# LEAKCAM.net
KiCad netlist of a schematic drawn in Altium Designer
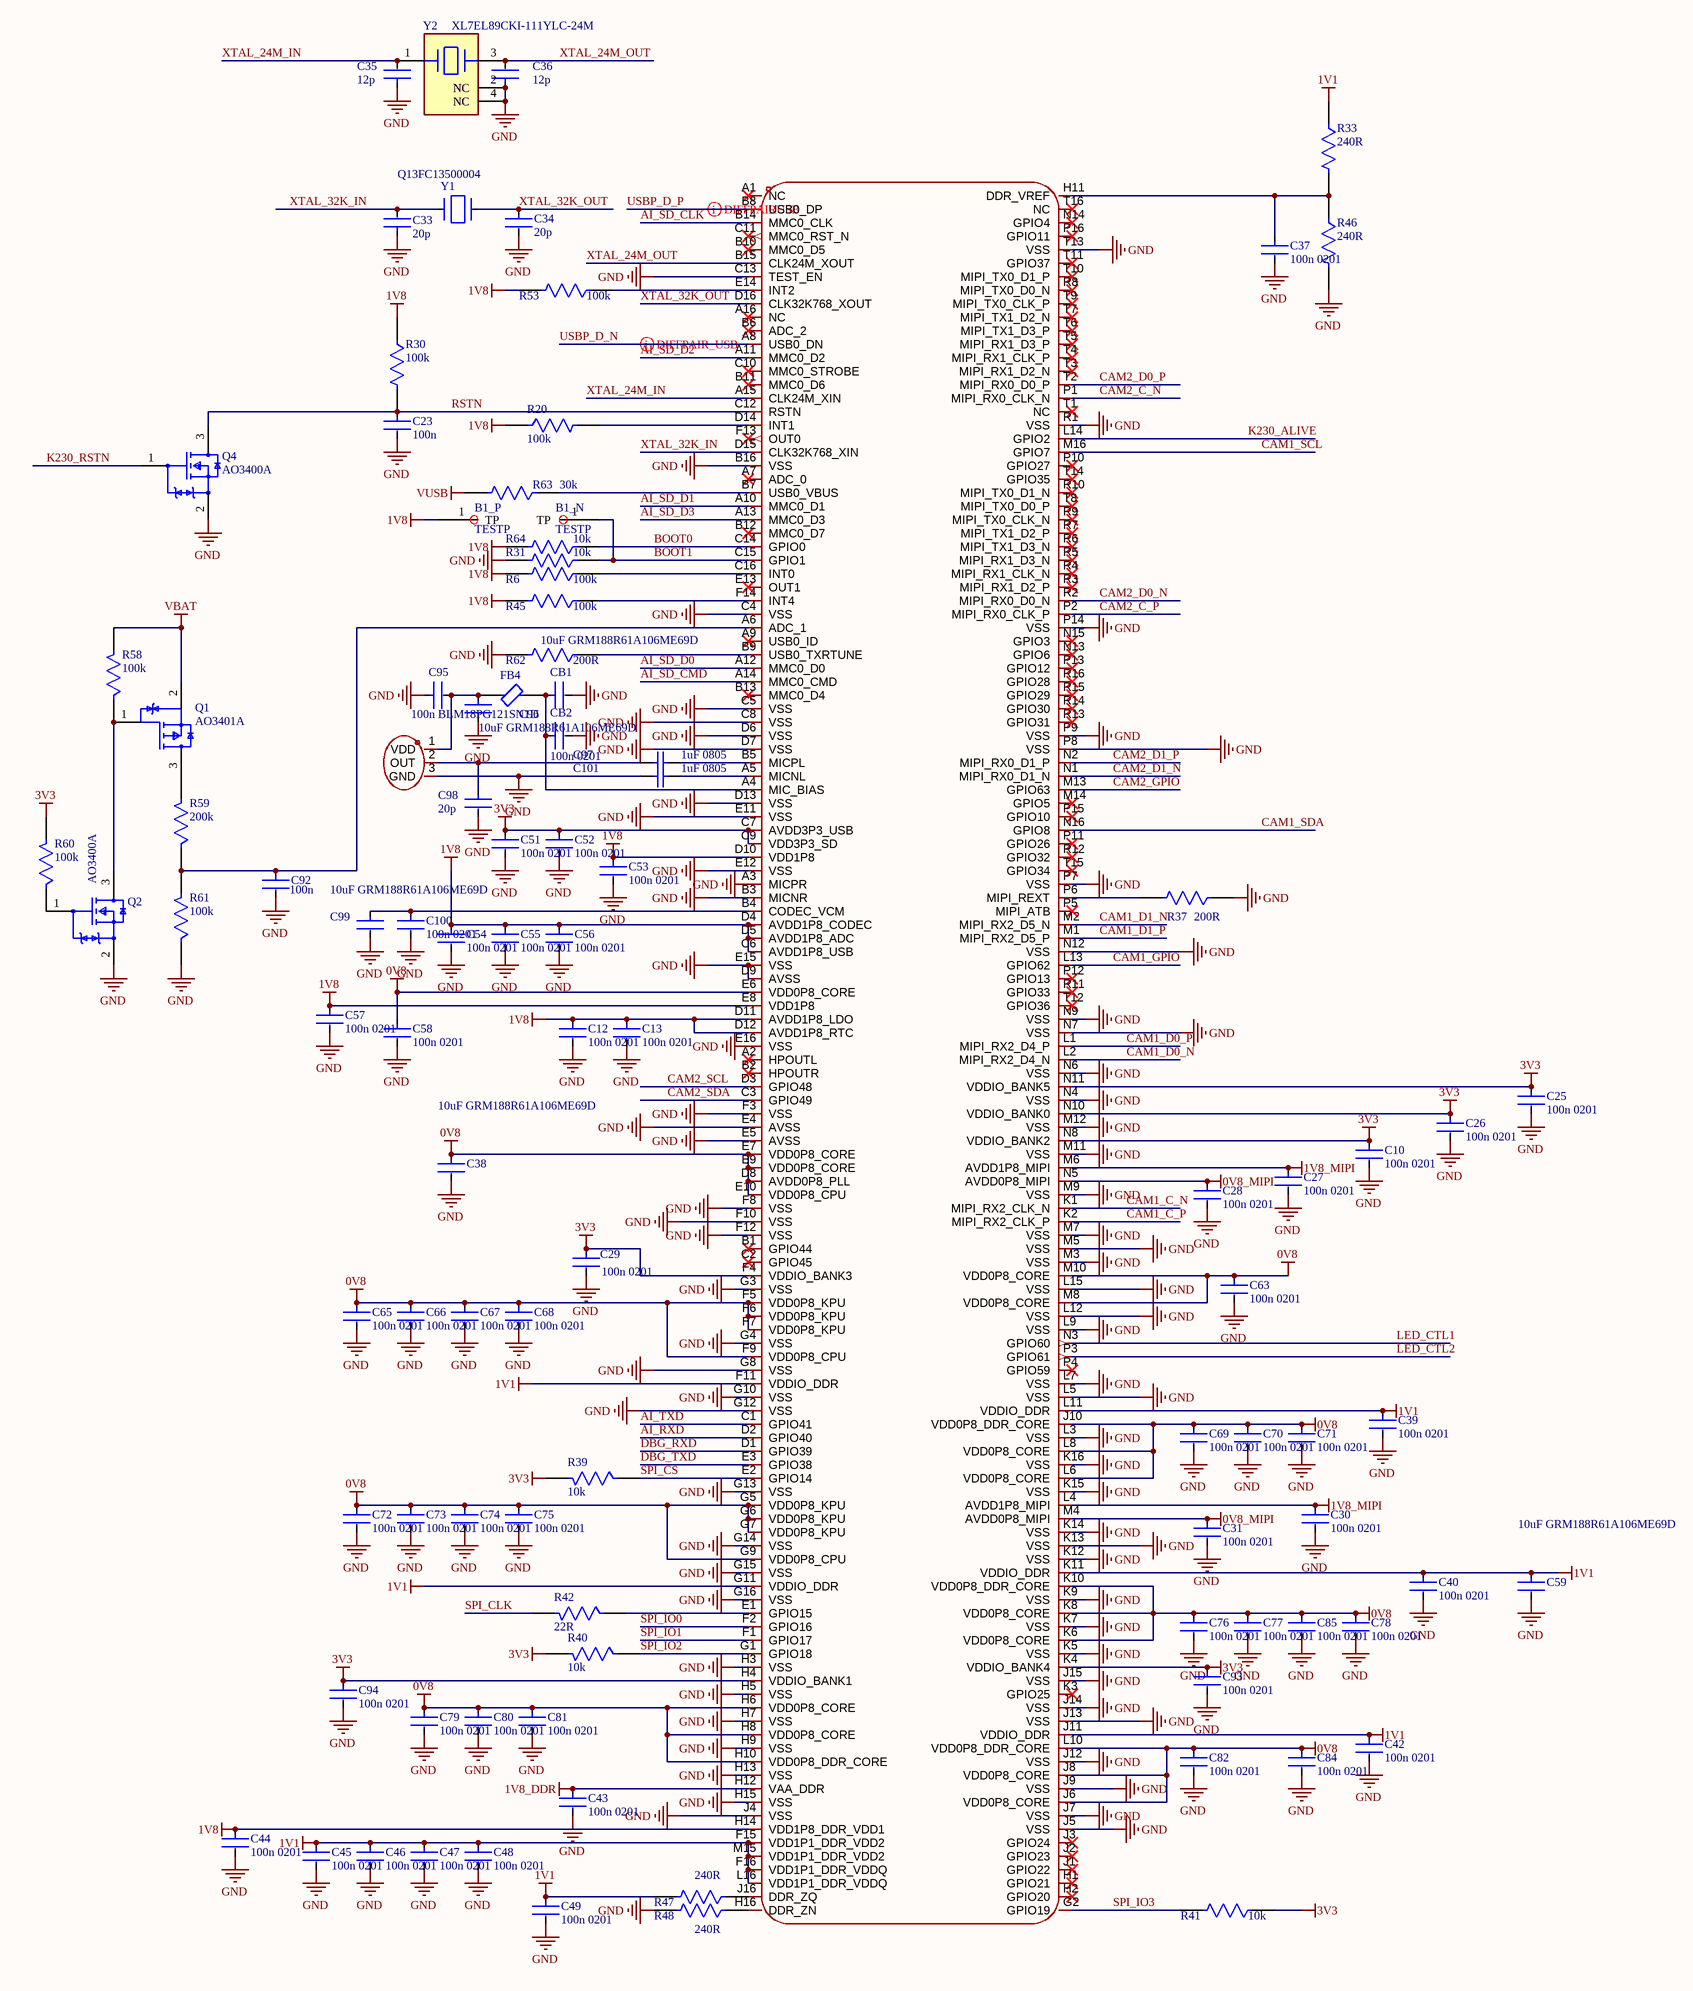
[diagram p0: LEAKCAM.SchDoc]

(export (version "E")
  (design (tool "Eeschema 10.0.6"))
  (components
    (comp (ref "B1_N") (value "TESTP") (footprint "TESTP") (libsource (lib "LEAKCAM") (part "TESTP")))
    (comp (ref "B1_P") (value "TESTP") (footprint "TESTP") (libsource (lib "LEAKCAM") (part "TESTP")))
    (comp (ref "C10")
      (value "100n 0201")
      (footprint "CAP_0201")
      (description "C2903663")
      (fields (field (name "TOLERANCE") "0.1") (field (name "MANUFACTURER") "Yageo"))
      (libsource (lib "LEAKCAM") (part "CMP-03422-001116-1"))
    )
    (comp (ref "C12")
      (value "100n 0201")
      (footprint "CAP_0201")
      (description "C2903663")
      (fields (field (name "TOLERANCE") "0.1") (field (name "MANUFACTURER") "Yageo"))
      (libsource (lib "LEAKCAM") (part "CMP-03422-001116-1"))
    )
    (comp (ref "C13")
      (value "100n 0201")
      (footprint "CAP_0201")
      (description "C2903663")
      (fields (field (name "TOLERANCE") "0.1") (field (name "MANUFACTURER") "Yageo"))
      (libsource (lib "LEAKCAM") (part "CMP-03422-001116-1"))
    )
    (comp (ref "C23")
      (value "100n")
      (footprint "CAP_0402")
      (description "C307331")
      (fields (field (name "TOLERANCE") "10%"))
      (libsource (lib "LEAKCAM") (part "CMP-03422-001116-1"))
    )
    (comp (ref "C25")
      (value "100n 0201")
      (footprint "CAP_0201")
      (description "C2903663")
      (fields (field (name "TOLERANCE") "0.1") (field (name "MANUFACTURER") "Yageo"))
      (libsource (lib "LEAKCAM") (part "CMP-03422-001116-1"))
    )
    (comp (ref "C26")
      (value "100n 0201")
      (footprint "CAP_0201")
      (description "C2903663")
      (fields (field (name "TOLERANCE") "0.1") (field (name "MANUFACTURER") "Yageo"))
      (libsource (lib "LEAKCAM") (part "CMP-03422-001116-1"))
    )
    (comp (ref "C27")
      (value "100n 0201")
      (footprint "CAP_0201")
      (description "C2903663")
      (fields (field (name "TOLERANCE") "0.1") (field (name "MANUFACTURER") "Yageo"))
      (libsource (lib "LEAKCAM") (part "CMP-03422-001116-1"))
    )
    (comp (ref "C28")
      (value "100n 0201")
      (footprint "CAP_0201")
      (description "C2903663")
      (fields (field (name "TOLERANCE") "0.1") (field (name "MANUFACTURER") "Yageo"))
      (libsource (lib "LEAKCAM") (part "CMP-03422-001116-1"))
    )
    (comp (ref "C29")
      (value "100n 0201")
      (footprint "CAP_0201")
      (description "C2903663")
      (fields (field (name "TOLERANCE") "0.1") (field (name "MANUFACTURER") "Yageo"))
      (libsource (lib "LEAKCAM") (part "CMP-03422-001116-1"))
    )
    (comp (ref "C30")
      (value "100n 0201")
      (footprint "CAP_0201")
      (description "C2903663")
      (fields (field (name "TOLERANCE") "0.1") (field (name "MANUFACTURER") "Yageo"))
      (libsource (lib "LEAKCAM") (part "CMP-03422-001116-1"))
    )
    (comp (ref "C31")
      (value "100n 0201")
      (footprint "CAP_0201")
      (description "C2903663")
      (fields (field (name "TOLERANCE") "0.1") (field (name "MANUFACTURER") "Yageo"))
      (libsource (lib "LEAKCAM") (part "CMP-03422-001116-1"))
    )
    (comp (ref "C33")
      (value "20p")
      (footprint "CAP_0402")
      (description "C1554")
      (fields (field (name "TOLERANCE") "10%"))
      (libsource (lib "LEAKCAM") (part "CMP-03422-001116-1"))
    )
    (comp (ref "C34")
      (value "20p")
      (footprint "CAP_0402")
      (description "C1554")
      (fields (field (name "TOLERANCE") "10%"))
      (libsource (lib "LEAKCAM") (part "CMP-03422-001116-1"))
    )
    (comp (ref "C35")
      (value "12p")
      (footprint "CAP_0402")
      (description "C1547")
      (fields (field (name "TOLERANCE") "10%"))
      (libsource (lib "LEAKCAM") (part "CMP-03422-001116-1"))
    )
    (comp (ref "C36")
      (value "12p")
      (footprint "CAP_0402")
      (description "C1547")
      (fields (field (name "TOLERANCE") "10%"))
      (libsource (lib "LEAKCAM") (part "CMP-03422-001116-1"))
    )
    (comp (ref "C37")
      (value "100n 0201")
      (footprint "CAP_0201")
      (description "C2903663")
      (fields (field (name "TOLERANCE") "0.1") (field (name "MANUFACTURER") "Yageo"))
      (libsource (lib "LEAKCAM") (part "CMP-03422-001116-1"))
    )
    (comp (ref "C38")
      (value "10uF GRM188R61A106ME69D")
      (footprint "FP-GRM188-0_15-MFG")
      (description "C19702")
      (fields (field (name "TOLERANCE") "20%"))
      (libsource (lib "LEAKCAM") (part "CMP-06035-003612-1"))
    )
    (comp (ref "C39")
      (value "100n 0201")
      (footprint "CAP_0201")
      (description "C2903663")
      (fields (field (name "TOLERANCE") "0.1") (field (name "MANUFACTURER") "Yageo"))
      (libsource (lib "LEAKCAM") (part "CMP-03422-001116-1"))
    )
    (comp (ref "C40")
      (value "100n 0201")
      (footprint "CAP_0201")
      (description "C2903663")
      (fields (field (name "TOLERANCE") "0.1") (field (name "MANUFACTURER") "Yageo"))
      (libsource (lib "LEAKCAM") (part "CMP-03422-001116-1"))
    )
    (comp (ref "C42")
      (value "100n 0201")
      (footprint "CAP_0201")
      (description "C2903663")
      (fields (field (name "TOLERANCE") "0.1") (field (name "MANUFACTURER") "Yageo"))
      (libsource (lib "LEAKCAM") (part "CMP-03422-001116-1"))
    )
    (comp (ref "C43")
      (value "100n 0201")
      (footprint "CAP_0201")
      (description "C2903663")
      (fields (field (name "TOLERANCE") "0.1") (field (name "MANUFACTURER") "Yageo"))
      (libsource (lib "LEAKCAM") (part "CMP-03422-001116-1"))
    )
    (comp (ref "C44")
      (value "100n 0201")
      (footprint "CAP_0201")
      (description "C2903663")
      (fields (field (name "TOLERANCE") "0.1") (field (name "MANUFACTURER") "Yageo"))
      (libsource (lib "LEAKCAM") (part "CMP-03422-001116-1"))
    )
    (comp (ref "C45")
      (value "100n 0201")
      (footprint "CAP_0201")
      (description "C2903663")
      (fields (field (name "TOLERANCE") "0.1") (field (name "MANUFACTURER") "Yageo"))
      (libsource (lib "LEAKCAM") (part "CMP-03422-001116-1"))
    )
    (comp (ref "C46")
      (value "100n 0201")
      (footprint "CAP_0201")
      (description "C2903663")
      (fields (field (name "TOLERANCE") "0.1") (field (name "MANUFACTURER") "Yageo"))
      (libsource (lib "LEAKCAM") (part "CMP-03422-001116-1"))
    )
    (comp (ref "C47")
      (value "100n 0201")
      (footprint "CAP_0201")
      (description "C2903663")
      (fields (field (name "TOLERANCE") "0.1") (field (name "MANUFACTURER") "Yageo"))
      (libsource (lib "LEAKCAM") (part "CMP-03422-001116-1"))
    )
    (comp (ref "C48")
      (value "100n 0201")
      (footprint "CAP_0201")
      (description "C2903663")
      (fields (field (name "TOLERANCE") "0.1") (field (name "MANUFACTURER") "Yageo"))
      (libsource (lib "LEAKCAM") (part "CMP-03422-001116-1"))
    )
    (comp (ref "C49")
      (value "100n 0201")
      (footprint "CAP_0201")
      (description "C2903663")
      (fields (field (name "TOLERANCE") "0.1") (field (name "MANUFACTURER") "Yageo"))
      (libsource (lib "LEAKCAM") (part "CMP-03422-001116-1"))
    )
    (comp (ref "C51")
      (value "100n 0201")
      (footprint "CAP_0201")
      (description "C2903663")
      (fields (field (name "TOLERANCE") "0.1") (field (name "MANUFACTURER") "Yageo"))
      (libsource (lib "LEAKCAM") (part "CMP-03422-001116-1"))
    )
    (comp (ref "C52")
      (value "100n 0201")
      (footprint "CAP_0201")
      (description "C2903663")
      (fields (field (name "TOLERANCE") "0.1") (field (name "MANUFACTURER") "Yageo"))
      (libsource (lib "LEAKCAM") (part "CMP-03422-001116-1"))
    )
    (comp (ref "C53")
      (value "100n 0201")
      (footprint "CAP_0201")
      (description "C2903663")
      (fields (field (name "TOLERANCE") "0.1") (field (name "MANUFACTURER") "Yageo"))
      (libsource (lib "LEAKCAM") (part "CMP-03422-001116-1"))
    )
    (comp (ref "C54")
      (value "100n 0201")
      (footprint "CAP_0201")
      (description "C2903663")
      (fields (field (name "TOLERANCE") "0.1") (field (name "MANUFACTURER") "Yageo"))
      (libsource (lib "LEAKCAM") (part "CMP-03422-001116-1"))
    )
    (comp (ref "C55")
      (value "100n 0201")
      (footprint "CAP_0201")
      (description "C2903663")
      (fields (field (name "TOLERANCE") "0.1") (field (name "MANUFACTURER") "Yageo"))
      (libsource (lib "LEAKCAM") (part "CMP-03422-001116-1"))
    )
    (comp (ref "C56")
      (value "100n 0201")
      (footprint "CAP_0201")
      (description "C2903663")
      (fields (field (name "TOLERANCE") "0.1") (field (name "MANUFACTURER") "Yageo"))
      (libsource (lib "LEAKCAM") (part "CMP-03422-001116-1"))
    )
    (comp (ref "C57")
      (value "100n 0201")
      (footprint "CAP_0201")
      (description "C2903663")
      (fields (field (name "TOLERANCE") "0.1") (field (name "MANUFACTURER") "Yageo"))
      (libsource (lib "LEAKCAM") (part "CMP-03422-001116-1"))
    )
    (comp (ref "C58")
      (value "100n 0201")
      (footprint "CAP_0201")
      (description "C2903663")
      (fields (field (name "TOLERANCE") "0.1") (field (name "MANUFACTURER") "Yageo"))
      (libsource (lib "LEAKCAM") (part "CMP-03422-001116-1"))
    )
    (comp (ref "C59")
      (value "10uF GRM188R61A106ME69D")
      (footprint "FP-GRM188-0_15-MFG")
      (description "C19702")
      (fields (field (name "TOLERANCE") "20%"))
      (libsource (lib "LEAKCAM") (part "CMP-06035-003612-1"))
    )
    (comp (ref "C63")
      (value "100n 0201")
      (footprint "CAP_0201")
      (description "C2903663")
      (fields (field (name "TOLERANCE") "0.1") (field (name "MANUFACTURER") "Yageo"))
      (libsource (lib "LEAKCAM") (part "CMP-03422-001116-1"))
    )
    (comp (ref "C65")
      (value "100n 0201")
      (footprint "CAP_0201")
      (description "C2903663")
      (fields (field (name "TOLERANCE") "0.1") (field (name "MANUFACTURER") "Yageo"))
      (libsource (lib "LEAKCAM") (part "CMP-03422-001116-1"))
    )
    (comp (ref "C66")
      (value "100n 0201")
      (footprint "CAP_0201")
      (description "C2903663")
      (fields (field (name "TOLERANCE") "0.1") (field (name "MANUFACTURER") "Yageo"))
      (libsource (lib "LEAKCAM") (part "CMP-03422-001116-1"))
    )
    (comp (ref "C67")
      (value "100n 0201")
      (footprint "CAP_0201")
      (description "C2903663")
      (fields (field (name "TOLERANCE") "0.1") (field (name "MANUFACTURER") "Yageo"))
      (libsource (lib "LEAKCAM") (part "CMP-03422-001116-1"))
    )
    (comp (ref "C68")
      (value "100n 0201")
      (footprint "CAP_0201")
      (description "C2903663")
      (fields (field (name "TOLERANCE") "0.1") (field (name "MANUFACTURER") "Yageo"))
      (libsource (lib "LEAKCAM") (part "CMP-03422-001116-1"))
    )
    (comp (ref "C69")
      (value "100n 0201")
      (footprint "CAP_0201")
      (description "C2903663")
      (fields (field (name "TOLERANCE") "0.1") (field (name "MANUFACTURER") "Yageo"))
      (libsource (lib "LEAKCAM") (part "CMP-03422-001116-1"))
    )
    (comp (ref "C70")
      (value "100n 0201")
      (footprint "CAP_0201")
      (description "C2903663")
      (fields (field (name "TOLERANCE") "0.1") (field (name "MANUFACTURER") "Yageo"))
      (libsource (lib "LEAKCAM") (part "CMP-03422-001116-1"))
    )
    (comp (ref "C71")
      (value "100n 0201")
      (footprint "CAP_0201")
      (description "C2903663")
      (fields (field (name "TOLERANCE") "0.1") (field (name "MANUFACTURER") "Yageo"))
      (libsource (lib "LEAKCAM") (part "CMP-03422-001116-1"))
    )
    (comp (ref "C72")
      (value "100n 0201")
      (footprint "CAP_0201")
      (description "C2903663")
      (fields (field (name "TOLERANCE") "0.1") (field (name "MANUFACTURER") "Yageo"))
      (libsource (lib "LEAKCAM") (part "CMP-03422-001116-1"))
    )
    (comp (ref "C73")
      (value "100n 0201")
      (footprint "CAP_0201")
      (description "C2903663")
      (fields (field (name "TOLERANCE") "0.1") (field (name "MANUFACTURER") "Yageo"))
      (libsource (lib "LEAKCAM") (part "CMP-03422-001116-1"))
    )
    (comp (ref "C74")
      (value "100n 0201")
      (footprint "CAP_0201")
      (description "C2903663")
      (fields (field (name "TOLERANCE") "0.1") (field (name "MANUFACTURER") "Yageo"))
      (libsource (lib "LEAKCAM") (part "CMP-03422-001116-1"))
    )
    (comp (ref "C75")
      (value "100n 0201")
      (footprint "CAP_0201")
      (description "C2903663")
      (fields (field (name "TOLERANCE") "0.1") (field (name "MANUFACTURER") "Yageo"))
      (libsource (lib "LEAKCAM") (part "CMP-03422-001116-1"))
    )
    (comp (ref "C76")
      (value "100n 0201")
      (footprint "CAP_0201")
      (description "C2903663")
      (fields (field (name "TOLERANCE") "0.1") (field (name "MANUFACTURER") "Yageo"))
      (libsource (lib "LEAKCAM") (part "CMP-03422-001116-1"))
    )
    (comp (ref "C77")
      (value "100n 0201")
      (footprint "CAP_0201")
      (description "C2903663")
      (fields (field (name "TOLERANCE") "0.1") (field (name "MANUFACTURER") "Yageo"))
      (libsource (lib "LEAKCAM") (part "CMP-03422-001116-1"))
    )
    (comp (ref "C78")
      (value "100n 0201")
      (footprint "CAP_0201")
      (description "C2903663")
      (fields (field (name "TOLERANCE") "0.1") (field (name "MANUFACTURER") "Yageo"))
      (libsource (lib "LEAKCAM") (part "CMP-03422-001116-1"))
    )
    (comp (ref "C79")
      (value "100n 0201")
      (footprint "CAP_0201")
      (description "C2903663")
      (fields (field (name "TOLERANCE") "0.1") (field (name "MANUFACTURER") "Yageo"))
      (libsource (lib "LEAKCAM") (part "CMP-03422-001116-1"))
    )
    (comp (ref "C80")
      (value "100n 0201")
      (footprint "CAP_0201")
      (description "C2903663")
      (fields (field (name "TOLERANCE") "0.1") (field (name "MANUFACTURER") "Yageo"))
      (libsource (lib "LEAKCAM") (part "CMP-03422-001116-1"))
    )
    (comp (ref "C81")
      (value "100n 0201")
      (footprint "CAP_0201")
      (description "C2903663")
      (fields (field (name "TOLERANCE") "0.1") (field (name "MANUFACTURER") "Yageo"))
      (libsource (lib "LEAKCAM") (part "CMP-03422-001116-1"))
    )
    (comp (ref "C82")
      (value "100n 0201")
      (footprint "CAP_0201")
      (description "C2903663")
      (fields (field (name "TOLERANCE") "0.1") (field (name "MANUFACTURER") "Yageo"))
      (libsource (lib "LEAKCAM") (part "CMP-03422-001116-1"))
    )
    (comp (ref "C84")
      (value "100n 0201")
      (footprint "CAP_0201")
      (description "C2903663")
      (fields (field (name "TOLERANCE") "0.1") (field (name "MANUFACTURER") "Yageo"))
      (libsource (lib "LEAKCAM") (part "CMP-03422-001116-1"))
    )
    (comp (ref "C85")
      (value "100n 0201")
      (footprint "CAP_0201")
      (description "C2903663")
      (fields (field (name "TOLERANCE") "0.1") (field (name "MANUFACTURER") "Yageo"))
      (libsource (lib "LEAKCAM") (part "CMP-03422-001116-1"))
    )
    (comp (ref "C92")
      (value "100n")
      (footprint "CAP_0402")
      (description "C307331")
      (fields (field (name "TOLERANCE") "10%"))
      (libsource (lib "LEAKCAM") (part "CMP-03422-001116-1"))
    )
    (comp (ref "C93")
      (value "100n 0201")
      (footprint "CAP_0201")
      (description "C2903663")
      (fields (field (name "TOLERANCE") "0.1") (field (name "MANUFACTURER") "Yageo"))
      (libsource (lib "LEAKCAM") (part "CMP-03422-001116-1"))
    )
    (comp (ref "C94")
      (value "100n 0201")
      (footprint "CAP_0201")
      (description "C2903663")
      (fields (field (name "TOLERANCE") "0.1") (field (name "MANUFACTURER") "Yageo"))
      (libsource (lib "LEAKCAM") (part "CMP-03422-001116-1"))
    )
    (comp (ref "C95")
      (value "100n")
      (footprint "CAP_0402")
      (description "C307331")
      (fields (field (name "TOLERANCE") "10%"))
      (libsource (lib "LEAKCAM") (part "CMP-03422-001116-1"))
    )
    (comp (ref "C96")
      (value "10uF GRM188R61A106ME69D")
      (footprint "FP-GRM188-0_15-MFG")
      (description "C19702")
      (fields (field (name "TOLERANCE") "20%"))
      (libsource (lib "LEAKCAM") (part "CMP-06035-003612-1"))
    )
    (comp (ref "C97")
      (value "1uF 0805")
      (footprint "CAPC2013X145X50NL20T20")
      (description "C28323")
      (fields (field (name "PART NUMBER") "VJ0805Y105KXQRW1BC") (field (name "MANUFACTURER") "Vitramon"))
      (libsource (lib "LEAKCAM") (part "CMP-2007-01676-1"))
    )
    (comp (ref "C98")
      (value "20p")
      (footprint "CAP_0402")
      (description "C1554")
      (fields (field (name "TOLERANCE") "10%"))
      (libsource (lib "LEAKCAM") (part "CMP-03422-001116-1"))
    )
    (comp (ref "C99")
      (value "10uF GRM188R61A106ME69D")
      (footprint "FP-GRM188-0_15-MFG")
      (description "C19702")
      (fields (field (name "TOLERANCE") "20%"))
      (libsource (lib "LEAKCAM") (part "CMP-06035-003612-1"))
    )
    (comp (ref "C100")
      (value "100n 0201")
      (footprint "CAP_0201")
      (description "C2903663")
      (fields (field (name "TOLERANCE") "0.1") (field (name "MANUFACTURER") "Yageo"))
      (libsource (lib "LEAKCAM") (part "CMP-03422-001116-1"))
    )
    (comp (ref "C101")
      (value "1uF 0805")
      (footprint "CAPC2013X145X50NL20T20")
      (description "C28323")
      (fields (field (name "PART NUMBER") "VJ0805Y105KXQRW1BC") (field (name "MANUFACTURER") "Vitramon"))
      (libsource (lib "LEAKCAM") (part "CMP-2007-01676-1"))
    )
    (comp (ref "CB1")
      (value "10uF GRM188R61A106ME69D")
      (footprint "FP-GRM188-0_15-MFG")
      (description "C19702")
      (fields (field (name "TOLERANCE") "20%"))
      (libsource (lib "LEAKCAM") (part "CMP-06035-003612-1"))
    )
    (comp (ref "CB2")
      (value "100n 0201")
      (footprint "CAP_0201")
      (description "C2903663")
      (fields (field (name "TOLERANCE") "0.1") (field (name "MANUFACTURER") "Yageo"))
      (libsource (lib "LEAKCAM") (part "CMP-03422-001116-1"))
    )
    (comp (ref "FB4")
      (value "BLM18PG121SN1D")
      (footprint "FP-BLM18-0_15-t0_8-IPC_B")
      (description "C14709")
      (fields (field (name "TOLERANCE") "25%"))
      (libsource (lib "LEAKCAM") (part "CMP-0686-00439-3"))
    )
    (comp (ref "Q1")
      (value "AO3401A")
      (footprint "FP-SOT23-IPC_B")
      (description "C15127")
      (libsource (lib "LEAKCAM") (part "CMP-12801-000081-1"))
    )
    (comp (ref "Q2")
      (value "AO3400A")
      (footprint "FP-SOT23-MFG")
      (description "C20917")
      (fields
        (field (name "MANUFACTURER PART NUMBER") "DMG2302UK-7")
        (field (name "OCTOPART") "https://octopart.com/dmg2302uk-7-diodes+inc.-73850182")
      )
      (libsource (lib "LEAKCAM") (part "CMP-12801-000001-1"))
    )
    (comp (ref "Q4")
      (value "AO3400A")
      (footprint "FP-SOT23-MFG")
      (description "C20917")
      (fields
        (field (name "MANUFACTURER PART NUMBER") "DMG2302UK-7")
        (field (name "OCTOPART") "https://octopart.com/dmg2302uk-7-diodes+inc.-73850182")
      )
      (libsource (lib "LEAKCAM") (part "CMP-12801-000001-1"))
    )
    (comp (ref "R6")
      (value "100k")
      (footprint "RES_0402")
      (description "C25741")
      (fields (field (name "TOLERANCE") "1%"))
      (libsource (lib "LEAKCAM") (part "CMP-03412-016018-1"))
    )
    (comp (ref "R20")
      (value "100k")
      (footprint "RES_0402")
      (description "C25741")
      (fields (field (name "TOLERANCE") "1%"))
      (libsource (lib "LEAKCAM") (part "CMP-03412-016018-1"))
    )
    (comp (ref "R30")
      (value "100k")
      (footprint "RES_0402")
      (description "C25741")
      (fields (field (name "TOLERANCE") "1%"))
      (libsource (lib "LEAKCAM") (part "CMP-03412-016018-1"))
    )
    (comp (ref "R31")
      (value "10k")
      (footprint "RES_0402")
      (description "C25744")
      (fields (field (name "TOLERANCE") "1%"))
      (libsource (lib "LEAKCAM") (part "CMP-03412-016018-1"))
    )
    (comp (ref "R33")
      (value "240R")
      (footprint "RES_0402")
      (description "C324768")
      (fields (field (name "TOLERANCE") "1%"))
      (libsource (lib "LEAKCAM") (part "CMP-03412-016018-1"))
    )
    (comp (ref "R37")
      (value "200R")
      (footprint "RES_0402")
      (description "C25087")
      (fields (field (name "TOLERANCE") "1%"))
      (libsource (lib "LEAKCAM") (part "CMP-03412-016018-1"))
    )
    (comp (ref "R39")
      (value "10k")
      (footprint "RES_0402")
      (description "C25744")
      (fields (field (name "TOLERANCE") "1%"))
      (libsource (lib "LEAKCAM") (part "CMP-03412-016018-1"))
    )
    (comp (ref "R40")
      (value "10k")
      (footprint "RES_0402")
      (description "C25744")
      (fields (field (name "TOLERANCE") "1%"))
      (libsource (lib "LEAKCAM") (part "CMP-03412-016018-1"))
    )
    (comp (ref "R41")
      (value "10k")
      (footprint "RES_0402")
      (description "C25744")
      (fields (field (name "TOLERANCE") "1%"))
      (libsource (lib "LEAKCAM") (part "CMP-03412-016018-1"))
    )
    (comp (ref "R42")
      (value "22R")
      (footprint "RES_0402")
      (description "C25092")
      (fields (field (name "TOLERANCE") "1%"))
      (libsource (lib "LEAKCAM") (part "CMP-03412-016018-1"))
    )
    (comp (ref "R45")
      (value "100k")
      (footprint "RES_0402")
      (description "C25741")
      (fields (field (name "TOLERANCE") "1%"))
      (libsource (lib "LEAKCAM") (part "CMP-03412-016018-1"))
    )
    (comp (ref "R46")
      (value "240R")
      (footprint "RES_0402")
      (description "C324768")
      (fields (field (name "TOLERANCE") "1%"))
      (libsource (lib "LEAKCAM") (part "CMP-03412-016018-1"))
    )
    (comp (ref "R47")
      (value "240R")
      (footprint "RES_0402")
      (description "C324768")
      (fields (field (name "TOLERANCE") "1%"))
      (libsource (lib "LEAKCAM") (part "CMP-03412-016018-1"))
    )
    (comp (ref "R48")
      (value "240R")
      (footprint "RES_0402")
      (description "C324768")
      (fields (field (name "TOLERANCE") "1%"))
      (libsource (lib "LEAKCAM") (part "CMP-03412-016018-1"))
    )
    (comp (ref "R53")
      (value "100k")
      (footprint "RES_0402")
      (description "C25741")
      (fields (field (name "TOLERANCE") "1%"))
      (libsource (lib "LEAKCAM") (part "CMP-03412-016018-1"))
    )
    (comp (ref "R58")
      (value "100k")
      (footprint "RES_0402")
      (description "C25741")
      (fields (field (name "TOLERANCE") "1%"))
      (libsource (lib "LEAKCAM") (part "CMP-03412-016018-1"))
    )
    (comp (ref "R59")
      (value "200k")
      (footprint "RES_0402")
      (description "C25764")
      (fields (field (name "TOLERANCE") "1%"))
      (libsource (lib "LEAKCAM") (part "CMP-03412-016018-1"))
    )
    (comp (ref "R60")
      (value "100k")
      (footprint "RES_0402")
      (description "C25741")
      (fields (field (name "TOLERANCE") "1%"))
      (libsource (lib "LEAKCAM") (part "CMP-03412-016018-1"))
    )
    (comp (ref "R61")
      (value "100k")
      (footprint "RES_0402")
      (description "C25741")
      (fields (field (name "TOLERANCE") "1%"))
      (libsource (lib "LEAKCAM") (part "CMP-03412-016018-1"))
    )
    (comp (ref "R62")
      (value "200R")
      (footprint "RES_0402")
      (description "C25087")
      (fields (field (name "TOLERANCE") "1%"))
      (libsource (lib "LEAKCAM") (part "CMP-03412-016018-1"))
    )
    (comp (ref "R63")
      (value "30k")
      (footprint "RES_0402")
      (description "C49653548")
      (fields (field (name "TOLERANCE") "1%"))
      (libsource (lib "LEAKCAM") (part "CMP-03412-016018-1"))
    )
    (comp (ref "R64")
      (value "10k")
      (footprint "RES_0402")
      (description "C25744")
      (fields (field (name "TOLERANCE") "1%"))
      (libsource (lib "LEAKCAM") (part "CMP-03412-016018-1"))
    )
    (comp (ref "U3")
      (value "k230d")
      (footprint "K230D")
      (description "C42414902")
      (fields (field (name "MANUFACTURER") "Canaan(嘉楠)") (field (name "MANUFACTURERPART") "K230D"))
      (libsource (lib "LEAKCAM") (part "k230d"))
    )
    (comp (ref "U13")
      (value "msm381acb026")
      (footprint "mems")
      (description "C51928208")
      (fields (field (name "MANUFACTURER") "MEMS(敏芯微)") (field (name "MANUFACTURERPART") "MSM381ACB026"))
      (libsource (lib "LEAKCAM") (part "msm381acb026"))
    )
    (comp (ref "Y1")
      (value "Q13FC13500004")
      (footprint "FP-ABS07-MFG")
      (description "C32346")
      (fields (field (name "TOLERANCE") "20ppm"))
      (libsource (lib "LEAKCAM") (part "CMP-0447-00001-4"))
    )
    (comp (ref "Y2")
      (value "XL7EL89CKI-111YLC-24M")
      (footprint "FP-XRCGB_F_N-MFG")
      (description "C2965580")
      (fields (field (name "TOLERANCE") "30ppm"))
      (libsource (lib "LEAKCAM") (part "CMP-06054-000017-1"))
    )
  )
  (nets
    (net (code "1") (name "/AI_RXD") (class "Default")
      (node (ref "U3") (pin "D2") (pinfunction "GPIO40_D2") (pintype "passive"))
    )
    (net (code "2") (name "/AI_SD_CLK") (class "Default")
      (node (ref "U3") (pin "B14") (pinfunction "MMC0_CLK_B14") (pintype "passive"))
    )
    (net (code "3") (name "/AI_SD_CMD") (class "Default")
      (node (ref "U3") (pin "A14") (pinfunction "MMC0_CMD_A14") (pintype "passive"))
    )
    (net (code "4") (name "/AI_SD_D0") (class "Default")
      (node (ref "U3") (pin "A12") (pinfunction "MMC0_D0_A12") (pintype "passive"))
    )
    (net (code "5") (name "/AI_SD_D1") (class "Default")
      (node (ref "U3") (pin "A10") (pinfunction "MMC0_D1_A10") (pintype "passive"))
    )
    (net (code "6") (name "/AI_SD_D2") (class "Default")
      (node (ref "U3") (pin "A11") (pinfunction "MMC0_D2_A11") (pintype "passive"))
    )
    (net (code "7") (name "/AI_SD_D3") (class "Default")
      (node (ref "U3") (pin "A13") (pinfunction "MMC0_D3_A13") (pintype "passive"))
    )
    (net (code "8") (name "/AI_TXD") (class "Default")
      (node (ref "U3") (pin "C1") (pinfunction "GPIO41_C1") (pintype "passive"))
    )
    (net (code "9") (name "/BOOT0") (class "Default")
      (node (ref "R64") (pin "1") (pinfunction "1_1") (pintype "passive"))
      (node (ref "U3") (pin "C14") (pinfunction "GPIO0_C14") (pintype "passive"))
    )
    (net (code "10") (name "/BOOT1") (class "Default")
      (node (ref "B1_N") (pin "1") (pinfunction "TP_1") (pintype "passive"))
      (node (ref "R31") (pin "1") (pinfunction "1_1") (pintype "passive"))
      (node (ref "U3") (pin "C15") (pinfunction "GPIO1_C15") (pintype "passive"))
    )
    (net (code "11") (name "/CAM1_C_N") (class "Default")
      (node (ref "U3") (pin "K1") (pinfunction "MIPI_RX2_CLK_N_K1") (pintype "passive"))
    )
    (net (code "12") (name "/CAM1_C_P") (class "Default")
      (node (ref "U3") (pin "K2") (pinfunction "MIPI_RX2_CLK_P_K2") (pintype "passive"))
    )
    (net (code "13") (name "/CAM1_D0_N") (class "Default")
      (node (ref "U3") (pin "L2") (pinfunction "MIPI_RX2_D4_N_L2") (pintype "passive"))
    )
    (net (code "14") (name "/CAM1_D0_P") (class "Default")
      (node (ref "U3") (pin "L1") (pinfunction "MIPI_RX2_D4_P_L1") (pintype "passive"))
    )
    (net (code "15") (name "/CAM1_D1_N") (class "Default")
      (node (ref "U3") (pin "M2") (pinfunction "MIPI_RX2_D5_N_M2") (pintype "passive"))
    )
    (net (code "16") (name "/CAM1_D1_P") (class "Default")
      (node (ref "U3") (pin "M1") (pinfunction "MIPI_RX2_D5_P_M1") (pintype "passive"))
    )
    (net (code "17") (name "/CAM1_GPIO") (class "Default")
      (node (ref "U3") (pin "L13") (pinfunction "GPIO62_L13") (pintype "passive"))
    )
    (net (code "18") (name "/CAM1_SCL") (class "Default")
      (node (ref "U3") (pin "M16") (pinfunction "GPIO7_M16") (pintype "passive"))
    )
    (net (code "19") (name "/CAM1_SDA") (class "Default")
      (node (ref "U3") (pin "N16") (pinfunction "GPIO8_N16") (pintype "passive"))
    )
    (net (code "20") (name "/CAM2_C_N") (class "Default")
      (node (ref "U3") (pin "P1") (pinfunction "MIPI_RX0_CLK_N_P1") (pintype "passive"))
    )
    (net (code "21") (name "/CAM2_C_P") (class "Default")
      (node (ref "U3") (pin "P2") (pinfunction "MIPI_RX0_CLK_P_P2") (pintype "passive"))
    )
    (net (code "22") (name "/CAM2_D0_N") (class "Default")
      (node (ref "U3") (pin "R2") (pinfunction "MIPI_RX0_D0_N_R2") (pintype "passive"))
    )
    (net (code "23") (name "/CAM2_D0_P") (class "Default")
      (node (ref "U3") (pin "T2") (pinfunction "MIPI_RX0_D0_P_T2") (pintype "passive"))
    )
    (net (code "24") (name "/CAM2_D1_N") (class "Default")
      (node (ref "U3") (pin "N1") (pinfunction "MIPI_RX0_D1_N_N1") (pintype "passive"))
    )
    (net (code "25") (name "/CAM2_D1_P") (class "Default")
      (node (ref "U3") (pin "N2") (pinfunction "MIPI_RX0_D1_P_N2") (pintype "passive"))
    )
    (net (code "26") (name "/CAM2_GPIO") (class "Default")
      (node (ref "U3") (pin "M13") (pinfunction "GPIO63_M13") (pintype "passive"))
    )
    (net (code "27") (name "/CAM2_SCL") (class "Default")
      (node (ref "U3") (pin "D3") (pinfunction "GPIO48_D3") (pintype "passive"))
    )
    (net (code "28") (name "/CAM2_SDA") (class "Default")
      (node (ref "U3") (pin "C3") (pinfunction "GPIO49_C3") (pintype "passive"))
    )
    (net (code "29") (name "/DBG_RXD") (class "Default")
      (node (ref "U3") (pin "D1") (pinfunction "GPIO39_D1") (pintype "passive"))
    )
    (net (code "30") (name "/DBG_TXD") (class "Default")
      (node (ref "U3") (pin "E3") (pinfunction "GPIO38_E3") (pintype "passive"))
    )
    (net (code "31") (name "/K230_ALIVE") (class "Default")
      (node (ref "U3") (pin "L14") (pinfunction "GPIO2_L14") (pintype "passive"))
    )
    (net (code "32") (name "/K230_RSTN") (class "Default")
      (node (ref "Q4") (pin "1") (pinfunction "G_1") (pintype "passive"))
    )
    (net (code "33") (name "/LED_CTL1") (class "Default")
      (node (ref "U3") (pin "N3") (pinfunction "GPIO60_N3") (pintype "output"))
    )
    (net (code "34") (name "/LED_CTL2") (class "Default")
      (node (ref "U3") (pin "P3") (pinfunction "GPIO61_P3") (pintype "output"))
    )
    (net (code "35") (name "/RSTN") (class "Default")
      (node (ref "C23") (pin "1") (pinfunction "1_1") (pintype "passive"))
      (node (ref "Q4") (pin "3") (pinfunction "D_3") (pintype "passive"))
      (node (ref "R30") (pin "2") (pinfunction "2_2") (pintype "passive"))
      (node (ref "U3") (pin "C12") (pinfunction "RSTN_C12") (pintype "passive"))
    )
    (net (code "36") (name "/SPI_CLK") (class "Default")
      (node (ref "R42") (pin "2") (pinfunction "2_2") (pintype "passive"))
    )
    (net (code "37") (name "/SPI_CS") (class "Default")
      (node (ref "R39") (pin "1") (pinfunction "1_1") (pintype "passive"))
      (node (ref "U3") (pin "E2") (pinfunction "GPIO14_E2") (pintype "passive"))
    )
    (net (code "38") (name "/SPI_IO0") (class "Default")
      (node (ref "U3") (pin "F2") (pinfunction "GPIO16_F2") (pintype "passive"))
    )
    (net (code "39") (name "/SPI_IO1") (class "Default")
      (node (ref "U3") (pin "F1") (pinfunction "GPIO17_F1") (pintype "passive"))
    )
    (net (code "40") (name "/SPI_IO2") (class "Default")
      (node (ref "R40") (pin "1") (pinfunction "1_1") (pintype "passive"))
      (node (ref "U3") (pin "G1") (pinfunction "GPIO18_G1") (pintype "passive"))
    )
    (net (code "41") (name "/SPI_IO3") (class "Default")
      (node (ref "R41") (pin "2") (pinfunction "2_2") (pintype "passive"))
      (node (ref "U3") (pin "G2") (pinfunction "GPIO19_G2") (pintype "passive"))
    )
    (net (code "42") (name "/USBP_D_N") (class "Default")
      (node (ref "U3") (pin "A8") (pinfunction "USB0_DN_A8") (pintype "passive"))
    )
    (net (code "43") (name "/USBP_D_P") (class "Default")
      (node (ref "U3") (pin "B8") (pinfunction "USB0_DP_B8") (pintype "passive"))
    )
    (net (code "44") (name "/XTAL_24M_IN") (class "Default")
      (node (ref "C35") (pin "2") (pinfunction "2_2") (pintype "passive"))
      (node (ref "U3") (pin "A15") (pinfunction "CLK24M_XIN_A15") (pintype "passive"))
      (node (ref "Y2") (pin "1") (pinfunction "1_Input/Output_1") (pintype "passive"))
    )
    (net (code "45") (name "/XTAL_24M_OUT") (class "Default")
      (node (ref "C36") (pin "2") (pinfunction "2_2") (pintype "passive"))
      (node (ref "U3") (pin "B15") (pinfunction "CLK24M_XOUT_B15") (pintype "passive"))
      (node (ref "Y2") (pin "3") (pinfunction "2_Input/Output_3") (pintype "passive"))
    )
    (net (code "46") (name "/XTAL_32K_IN") (class "Default")
      (node (ref "C33") (pin "2") (pinfunction "2_2") (pintype "passive"))
      (node (ref "U3") (pin "D15") (pinfunction "CLK32K768_XIN_D15") (pintype "passive"))
      (node (ref "Y1") (pin "1") (pinfunction "1_1") (pintype "passive"))
    )
    (net (code "47") (name "/XTAL_32K_OUT") (class "Default")
      (node (ref "C34") (pin "1") (pinfunction "1_1") (pintype "passive"))
      (node (ref "U3") (pin "D16") (pinfunction "CLK32K768_XOUT_D16") (pintype "passive"))
      (node (ref "Y1") (pin "2") (pinfunction "2_2") (pintype "passive"))
    )
    (net (code "48") (name "0V8") (class "Default")
      (node (ref "C38") (pin "1") (pinfunction "1_1") (pintype "passive"))
      (node (ref "C58") (pin "1") (pinfunction "1_1") (pintype "passive"))
      (node (ref "C63") (pin "1") (pinfunction "1_1") (pintype "passive"))
      (node (ref "C65") (pin "1") (pinfunction "1_1") (pintype "passive"))
      (node (ref "C66") (pin "1") (pinfunction "1_1") (pintype "passive"))
      (node (ref "C67") (pin "1") (pinfunction "1_1") (pintype "passive"))
      (node (ref "C68") (pin "1") (pinfunction "1_1") (pintype "passive"))
      (node (ref "C69") (pin "1") (pinfunction "1_1") (pintype "passive"))
      (node (ref "C70") (pin "1") (pinfunction "1_1") (pintype "passive"))
      (node (ref "C71") (pin "1") (pinfunction "1_1") (pintype "passive"))
      (node (ref "C72") (pin "1") (pinfunction "1_1") (pintype "passive"))
      (node (ref "C73") (pin "1") (pinfunction "1_1") (pintype "passive"))
      (node (ref "C74") (pin "1") (pinfunction "1_1") (pintype "passive"))
      (node (ref "C75") (pin "1") (pinfunction "1_1") (pintype "passive"))
      (node (ref "C76") (pin "1") (pinfunction "1_1") (pintype "passive"))
      (node (ref "C77") (pin "1") (pinfunction "1_1") (pintype "passive"))
      (node (ref "C78") (pin "1") (pinfunction "1_1") (pintype "passive"))
      (node (ref "C79") (pin "1") (pinfunction "1_1") (pintype "passive"))
      (node (ref "C80") (pin "1") (pinfunction "1_1") (pintype "passive"))
      (node (ref "C81") (pin "1") (pinfunction "1_1") (pintype "passive"))
      (node (ref "C82") (pin "1") (pinfunction "1_1") (pintype "passive"))
      (node (ref "C84") (pin "1") (pinfunction "1_1") (pintype "passive"))
      (node (ref "C85") (pin "1") (pinfunction "1_1") (pintype "passive"))
      (node (ref "U3") (pin "D8") (pinfunction "AVDD0P8_PLL_D8") (pintype "passive"))
      (node (ref "U3") (pin "E10") (pinfunction "VDD0P8_CPU_E10") (pintype "passive"))
      (node (ref "U3") (pin "E6") (pinfunction "VDD0P8_CORE_E6") (pintype "passive"))
      (node (ref "U3") (pin "E7") (pinfunction "VDD0P8_CORE_E7") (pintype "passive"))
      (node (ref "U3") (pin "E9") (pinfunction "VDD0P8_CORE_E9") (pintype "passive"))
      (node (ref "U3") (pin "F5") (pinfunction "VDD0P8_KPU_F5") (pintype "passive"))
      (node (ref "U3") (pin "F6") (pinfunction "VDD0P8_KPU_F6") (pintype "passive"))
      (node (ref "U3") (pin "F7") (pinfunction "VDD0P8_KPU_F7") (pintype "passive"))
      (node (ref "U3") (pin "F9") (pinfunction "VDD0P8_CPU_F9") (pintype "passive"))
      (node (ref "U3") (pin "G5") (pinfunction "VDD0P8_KPU_G5") (pintype "passive"))
      (node (ref "U3") (pin "G6") (pinfunction "VDD0P8_KPU_G6") (pintype "passive"))
      (node (ref "U3") (pin "G7") (pinfunction "VDD0P8_KPU_G7") (pintype "passive"))
      (node (ref "U3") (pin "G9") (pinfunction "VDD0P8_CPU_G9") (pintype "passive"))
      (node (ref "U3") (pin "H10") (pinfunction "VDD0P8_DDR_CORE_H10") (pintype "passive"))
      (node (ref "U3") (pin "H6") (pinfunction "VDD0P8_CORE_H6") (pintype "passive"))
      (node (ref "U3") (pin "H8") (pinfunction "VDD0P8_CORE_H8") (pintype "passive"))
      (node (ref "U3") (pin "J10") (pinfunction "VDD0P8_DDR_CORE_J10") (pintype "passive"))
      (node (ref "U3") (pin "J6") (pinfunction "VDD0P8_CORE_J6") (pintype "passive"))
      (node (ref "U3") (pin "J8") (pinfunction "VDD0P8_CORE_J8") (pintype "passive"))
      (node (ref "U3") (pin "K10") (pinfunction "VDD0P8_DDR_CORE_K10") (pintype "passive"))
      (node (ref "U3") (pin "K6") (pinfunction "VDD0P8_CORE_K6") (pintype "passive"))
      (node (ref "U3") (pin "K8") (pinfunction "VDD0P8_CORE_K8") (pintype "passive"))
      (node (ref "U3") (pin "L10") (pinfunction "VDD0P8_DDR_CORE_L10") (pintype "passive"))
      (node (ref "U3") (pin "L6") (pinfunction "VDD0P8_CORE_L6") (pintype "passive"))
      (node (ref "U3") (pin "L8") (pinfunction "VDD0P8_CORE_L8") (pintype "passive"))
      (node (ref "U3") (pin "M10") (pinfunction "VDD0P8_CORE_M10") (pintype "passive"))
      (node (ref "U3") (pin "M8") (pinfunction "VDD0P8_CORE_M8") (pintype "passive"))
    )
    (net (code "49") (name "0V8_MIPI") (class "Default")
      (node (ref "C28") (pin "1") (pinfunction "1_1") (pintype "passive"))
      (node (ref "C31") (pin "1") (pinfunction "1_1") (pintype "passive"))
      (node (ref "U3") (pin "M4") (pinfunction "AVDD0P8_MIPI_M4") (pintype "passive"))
      (node (ref "U3") (pin "N5") (pinfunction "AVDD0P8_MIPI_N5") (pintype "passive"))
    )
    (net (code "50") (name "1V1") (class "Default")
      (node (ref "C39") (pin "1") (pinfunction "1_1") (pintype "passive"))
      (node (ref "C40") (pin "1") (pinfunction "1_1") (pintype "passive"))
      (node (ref "C42") (pin "1") (pinfunction "1_1") (pintype "passive"))
      (node (ref "C45") (pin "1") (pinfunction "1_1") (pintype "passive"))
      (node (ref "C46") (pin "1") (pinfunction "1_1") (pintype "passive"))
      (node (ref "C47") (pin "1") (pinfunction "1_1") (pintype "passive"))
      (node (ref "C48") (pin "1") (pinfunction "1_1") (pintype "passive"))
      (node (ref "C49") (pin "1") (pinfunction "1_1") (pintype "passive"))
      (node (ref "C59") (pin "1") (pinfunction "1_1") (pintype "passive"))
      (node (ref "R33") (pin "1") (pinfunction "1_1") (pintype "passive"))
      (node (ref "R47") (pin "2") (pinfunction "2_2") (pintype "passive"))
      (node (ref "U3") (pin "F11") (pinfunction "VDDIO_DDR_F11") (pintype "passive"))
      (node (ref "U3") (pin "F15") (pinfunction "VDD1P1_DDR_VDD2_F15") (pintype "passive"))
      (node (ref "U3") (pin "F16") (pinfunction "VDD1P1_DDR_VDDQ_F16") (pintype "passive"))
      (node (ref "U3") (pin "G11") (pinfunction "VDDIO_DDR_G11") (pintype "passive"))
      (node (ref "U3") (pin "J11") (pinfunction "VDDIO_DDR_J11") (pintype "passive"))
      (node (ref "U3") (pin "K11") (pinfunction "VDDIO_DDR_K11") (pintype "passive"))
      (node (ref "U3") (pin "L11") (pinfunction "VDDIO_DDR_L11") (pintype "passive"))
      (node (ref "U3") (pin "L16") (pinfunction "VDD1P1_DDR_VDDQ_L16") (pintype "passive"))
      (node (ref "U3") (pin "M15") (pinfunction "VDD1P1_DDR_VDD2_M15") (pintype "passive"))
    )
    (net (code "51") (name "1V8") (class "Default")
      (node (ref "B1_P") (pin "1") (pinfunction "TP_1") (pintype "passive"))
      (node (ref "C12") (pin "1") (pinfunction "1_1") (pintype "passive"))
      (node (ref "C13") (pin "1") (pinfunction "1_1") (pintype "passive"))
      (node (ref "C44") (pin "1") (pinfunction "1_1") (pintype "passive"))
      (node (ref "C53") (pin "1") (pinfunction "1_1") (pintype "passive"))
      (node (ref "C54") (pin "1") (pinfunction "1_1") (pintype "passive"))
      (node (ref "C55") (pin "1") (pinfunction "1_1") (pintype "passive"))
      (node (ref "C56") (pin "1") (pinfunction "1_1") (pintype "passive"))
      (node (ref "C57") (pin "1") (pinfunction "1_1") (pintype "passive"))
      (node (ref "R20") (pin "1") (pinfunction "1_1") (pintype "passive"))
      (node (ref "R30") (pin "1") (pinfunction "1_1") (pintype "passive"))
      (node (ref "R45") (pin "2") (pinfunction "2_2") (pintype "passive"))
      (node (ref "R53") (pin "2") (pinfunction "2_2") (pintype "passive"))
      (node (ref "R6") (pin "2") (pinfunction "2_2") (pintype "passive"))
      (node (ref "R64") (pin "2") (pinfunction "2_2") (pintype "passive"))
      (node (ref "U3") (pin "C6") (pinfunction "AVDD1P8_USB_C6") (pintype "passive"))
      (node (ref "U3") (pin "D10") (pinfunction "VDD1P8_D10") (pintype "passive"))
      (node (ref "U3") (pin "D11") (pinfunction "AVDD1P8_LDO_D11") (pintype "passive"))
      (node (ref "U3") (pin "D12") (pinfunction "AVDD1P8_RTC_D12") (pintype "passive"))
      (node (ref "U3") (pin "D4") (pinfunction "AVDD1P8_CODEC_D4") (pintype "passive"))
      (node (ref "U3") (pin "D5") (pinfunction "AVDD1P8_ADC_D5") (pintype "passive"))
      (node (ref "U3") (pin "E8") (pinfunction "VDD1P8_E8") (pintype "passive"))
      (node (ref "U3") (pin "H14") (pinfunction "VDD1P8_DDR_VDD1_H14") (pintype "passive"))
    )
    (net (code "52") (name "1V8_DDR") (class "Default")
      (node (ref "C43") (pin "1") (pinfunction "1_1") (pintype "passive"))
      (node (ref "U3") (pin "H12") (pinfunction "VAA_DDR_H12") (pintype "passive"))
    )
    (net (code "53") (name "1V8_MIPI") (class "Default")
      (node (ref "C27") (pin "1") (pinfunction "1_1") (pintype "passive"))
      (node (ref "C30") (pin "1") (pinfunction "1_1") (pintype "passive"))
      (node (ref "U3") (pin "L4") (pinfunction "AVDD1P8_MIPI_L4") (pintype "passive"))
      (node (ref "U3") (pin "M6") (pinfunction "AVDD1P8_MIPI_M6") (pintype "passive"))
    )
    (net (code "54") (name "3V3") (class "Default")
      (node (ref "C10") (pin "1") (pinfunction "1_1") (pintype "passive"))
      (node (ref "C25") (pin "1") (pinfunction "1_1") (pintype "passive"))
      (node (ref "C26") (pin "1") (pinfunction "1_1") (pintype "passive"))
      (node (ref "C29") (pin "1") (pinfunction "1_1") (pintype "passive"))
      (node (ref "C51") (pin "1") (pinfunction "1_1") (pintype "passive"))
      (node (ref "C52") (pin "1") (pinfunction "1_1") (pintype "passive"))
      (node (ref "C93") (pin "1") (pinfunction "1_1") (pintype "passive"))
      (node (ref "C94") (pin "1") (pinfunction "1_1") (pintype "passive"))
      (node (ref "R39") (pin "2") (pinfunction "2_2") (pintype "passive"))
      (node (ref "R40") (pin "2") (pinfunction "2_2") (pintype "passive"))
      (node (ref "R41") (pin "1") (pinfunction "1_1") (pintype "passive"))
      (node (ref "R60") (pin "2") (pinfunction "2_2") (pintype "passive"))
      (node (ref "U3") (pin "C7") (pinfunction "AVDD3P3_USB_C7") (pintype "passive"))
      (node (ref "U3") (pin "C9") (pinfunction "VDD3P3_SD_C9") (pintype "passive"))
      (node (ref "U3") (pin "F4") (pinfunction "VDDIO_BANK3_F4") (pintype "passive"))
      (node (ref "U3") (pin "H4") (pinfunction "VDDIO_BANK1_H4") (pintype "passive"))
      (node (ref "U3") (pin "K4") (pinfunction "VDDIO_BANK4_K4") (pintype "passive"))
      (node (ref "U3") (pin "N10") (pinfunction "VDDIO_BANK0_N10") (pintype "passive"))
      (node (ref "U3") (pin "N11") (pinfunction "VDDIO_BANK5_N11") (pintype "passive"))
      (node (ref "U3") (pin "N8") (pinfunction "VDDIO_BANK2_N8") (pintype "passive"))
    )
    (net (code "55") (name "GND") (class "Default")
      (node (ref "C10") (pin "2") (pinfunction "2_2") (pintype "passive"))
      (node (ref "C100") (pin "2") (pinfunction "2_2") (pintype "passive"))
      (node (ref "C101") (pin "1") (pinfunction "1_1") (pintype "passive"))
      (node (ref "C12") (pin "2") (pinfunction "2_2") (pintype "passive"))
      (node (ref "C13") (pin "2") (pinfunction "2_2") (pintype "passive"))
      (node (ref "C23") (pin "2") (pinfunction "2_2") (pintype "passive"))
      (node (ref "C25") (pin "2") (pinfunction "2_2") (pintype "passive"))
      (node (ref "C26") (pin "2") (pinfunction "2_2") (pintype "passive"))
      (node (ref "C27") (pin "2") (pinfunction "2_2") (pintype "passive"))
      (node (ref "C28") (pin "2") (pinfunction "2_2") (pintype "passive"))
      (node (ref "C29") (pin "2") (pinfunction "2_2") (pintype "passive"))
      (node (ref "C30") (pin "2") (pinfunction "2_2") (pintype "passive"))
      (node (ref "C31") (pin "2") (pinfunction "2_2") (pintype "passive"))
      (node (ref "C33") (pin "1") (pinfunction "1_1") (pintype "passive"))
      (node (ref "C34") (pin "2") (pinfunction "2_2") (pintype "passive"))
      (node (ref "C35") (pin "1") (pinfunction "1_1") (pintype "passive"))
      (node (ref "C36") (pin "1") (pinfunction "1_1") (pintype "passive"))
      (node (ref "C37") (pin "2") (pinfunction "2_2") (pintype "passive"))
      (node (ref "C38") (pin "2") (pinfunction "2_2") (pintype "passive"))
      (node (ref "C39") (pin "2") (pinfunction "2_2") (pintype "passive"))
      (node (ref "C40") (pin "2") (pinfunction "2_2") (pintype "passive"))
      (node (ref "C42") (pin "2") (pinfunction "2_2") (pintype "passive"))
      (node (ref "C43") (pin "2") (pinfunction "2_2") (pintype "passive"))
      (node (ref "C44") (pin "2") (pinfunction "2_2") (pintype "passive"))
      (node (ref "C45") (pin "2") (pinfunction "2_2") (pintype "passive"))
      (node (ref "C46") (pin "2") (pinfunction "2_2") (pintype "passive"))
      (node (ref "C47") (pin "2") (pinfunction "2_2") (pintype "passive"))
      (node (ref "C48") (pin "2") (pinfunction "2_2") (pintype "passive"))
      (node (ref "C49") (pin "2") (pinfunction "2_2") (pintype "passive"))
      (node (ref "C51") (pin "2") (pinfunction "2_2") (pintype "passive"))
      (node (ref "C52") (pin "2") (pinfunction "2_2") (pintype "passive"))
      (node (ref "C53") (pin "2") (pinfunction "2_2") (pintype "passive"))
      (node (ref "C54") (pin "2") (pinfunction "2_2") (pintype "passive"))
      (node (ref "C55") (pin "2") (pinfunction "2_2") (pintype "passive"))
      (node (ref "C56") (pin "2") (pinfunction "2_2") (pintype "passive"))
      (node (ref "C57") (pin "2") (pinfunction "2_2") (pintype "passive"))
      (node (ref "C58") (pin "2") (pinfunction "2_2") (pintype "passive"))
      (node (ref "C59") (pin "2") (pinfunction "2_2") (pintype "passive"))
      (node (ref "C63") (pin "2") (pinfunction "2_2") (pintype "passive"))
      (node (ref "C65") (pin "2") (pinfunction "2_2") (pintype "passive"))
      (node (ref "C66") (pin "2") (pinfunction "2_2") (pintype "passive"))
      (node (ref "C67") (pin "2") (pinfunction "2_2") (pintype "passive"))
      (node (ref "C68") (pin "2") (pinfunction "2_2") (pintype "passive"))
      (node (ref "C69") (pin "2") (pinfunction "2_2") (pintype "passive"))
      (node (ref "C70") (pin "2") (pinfunction "2_2") (pintype "passive"))
      (node (ref "C71") (pin "2") (pinfunction "2_2") (pintype "passive"))
      (node (ref "C72") (pin "2") (pinfunction "2_2") (pintype "passive"))
      (node (ref "C73") (pin "2") (pinfunction "2_2") (pintype "passive"))
      (node (ref "C74") (pin "2") (pinfunction "2_2") (pintype "passive"))
      (node (ref "C75") (pin "2") (pinfunction "2_2") (pintype "passive"))
      (node (ref "C76") (pin "2") (pinfunction "2_2") (pintype "passive"))
      (node (ref "C77") (pin "2") (pinfunction "2_2") (pintype "passive"))
      (node (ref "C78") (pin "2") (pinfunction "2_2") (pintype "passive"))
      (node (ref "C79") (pin "2") (pinfunction "2_2") (pintype "passive"))
      (node (ref "C80") (pin "2") (pinfunction "2_2") (pintype "passive"))
      (node (ref "C81") (pin "2") (pinfunction "2_2") (pintype "passive"))
      (node (ref "C82") (pin "2") (pinfunction "2_2") (pintype "passive"))
      (node (ref "C84") (pin "2") (pinfunction "2_2") (pintype "passive"))
      (node (ref "C85") (pin "2") (pinfunction "2_2") (pintype "passive"))
      (node (ref "C92") (pin "2") (pinfunction "2_2") (pintype "passive"))
      (node (ref "C93") (pin "2") (pinfunction "2_2") (pintype "passive"))
      (node (ref "C94") (pin "2") (pinfunction "2_2") (pintype "passive"))
      (node (ref "C95") (pin "1") (pinfunction "1_1") (pintype "passive"))
      (node (ref "C96") (pin "2") (pinfunction "2_2") (pintype "passive"))
      (node (ref "C98") (pin "2") (pinfunction "2_2") (pintype "passive"))
      (node (ref "C99") (pin "2") (pinfunction "2_2") (pintype "passive"))
      (node (ref "CB1") (pin "2") (pinfunction "2_2") (pintype "passive"))
      (node (ref "CB2") (pin "2") (pinfunction "2_2") (pintype "passive"))
      (node (ref "Q2") (pin "2") (pinfunction "S_2") (pintype "passive"))
      (node (ref "Q4") (pin "2") (pinfunction "S_2") (pintype "passive"))
      (node (ref "R31") (pin "2") (pinfunction "2_2") (pintype "passive"))
      (node (ref "R37") (pin "1") (pinfunction "1_1") (pintype "passive"))
      (node (ref "R46") (pin "2") (pinfunction "2_2") (pintype "passive"))
      (node (ref "R48") (pin "2") (pinfunction "2_2") (pintype "passive"))
      (node (ref "R61") (pin "1") (pinfunction "1_1") (pintype "passive"))
      (node (ref "R62") (pin "2") (pinfunction "2_2") (pintype "passive"))
      (node (ref "U13") (pin "3") (pinfunction "GND_3") (pintype "passive"))
      (node (ref "U3") (pin "A3") (pinfunction "MICPR_A3") (pintype "passive"))
      (node (ref "U3") (pin "B16") (pinfunction "VSS_B16") (pintype "passive"))
      (node (ref "U3") (pin "B3") (pinfunction "MICNR_B3") (pintype "passive"))
      (node (ref "U3") (pin "C13") (pinfunction "TEST_EN_C13") (pintype "passive"))
      (node (ref "U3") (pin "C4") (pinfunction "VSS_C4") (pintype "passive"))
      (node (ref "U3") (pin "C5") (pinfunction "VSS_C5") (pintype "passive"))
      (node (ref "U3") (pin "C8") (pinfunction "VSS_C8") (pintype "passive"))
      (node (ref "U3") (pin "D13") (pinfunction "VSS_D13") (pintype "passive"))
      (node (ref "U3") (pin "D6") (pinfunction "VSS_D6") (pintype "passive"))
      (node (ref "U3") (pin "D7") (pinfunction "VSS_D7") (pintype "passive"))
      (node (ref "U3") (pin "D9") (pinfunction "AVSS_D9") (pintype "passive"))
      (node (ref "U3") (pin "E11") (pinfunction "VSS_E11") (pintype "passive"))
      (node (ref "U3") (pin "E12") (pinfunction "VSS_E12") (pintype "passive"))
      (node (ref "U3") (pin "E15") (pinfunction "VSS_E15") (pintype "passive"))
      (node (ref "U3") (pin "E16") (pinfunction "VSS_E16") (pintype "passive"))
      (node (ref "U3") (pin "E4") (pinfunction "AVSS_E4") (pintype "passive"))
      (node (ref "U3") (pin "E5") (pinfunction "AVSS_E5") (pintype "passive"))
      (node (ref "U3") (pin "F10") (pinfunction "VSS_F10") (pintype "passive"))
      (node (ref "U3") (pin "F12") (pinfunction "VSS_F12") (pintype "passive"))
      (node (ref "U3") (pin "F3") (pinfunction "VSS_F3") (pintype "passive"))
      (node (ref "U3") (pin "F8") (pinfunction "VSS_F8") (pintype "passive"))
      (node (ref "U3") (pin "G10") (pinfunction "VSS_G10") (pintype "passive"))
      (node (ref "U3") (pin "G12") (pinfunction "VSS_G12") (pintype "passive"))
      (node (ref "U3") (pin "G13") (pinfunction "VSS_G13") (pintype "passive"))
      (node (ref "U3") (pin "G14") (pinfunction "VSS_G14") (pintype "passive"))
      (node (ref "U3") (pin "G15") (pinfunction "VSS_G15") (pintype "passive"))
      (node (ref "U3") (pin "G16") (pinfunction "VSS_G16") (pintype "passive"))
      (node (ref "U3") (pin "G3") (pinfunction "VSS_G3") (pintype "passive"))
      (node (ref "U3") (pin "G4") (pinfunction "VSS_G4") (pintype "passive"))
      (node (ref "U3") (pin "G8") (pinfunction "VSS_G8") (pintype "passive"))
      (node (ref "U3") (pin "H13") (pinfunction "VSS_H13") (pintype "passive"))
      (node (ref "U3") (pin "H15") (pinfunction "VSS_H15") (pintype "passive"))
      (node (ref "U3") (pin "H3") (pinfunction "VSS_H3") (pintype "passive"))
      (node (ref "U3") (pin "H5") (pinfunction "VSS_H5") (pintype "passive"))
      (node (ref "U3") (pin "H7") (pinfunction "VSS_H7") (pintype "passive"))
      (node (ref "U3") (pin "H9") (pinfunction "VSS_H9") (pintype "passive"))
      (node (ref "U3") (pin "J12") (pinfunction "VSS_J12") (pintype "passive"))
      (node (ref "U3") (pin "J13") (pinfunction "VSS_J13") (pintype "passive"))
      (node (ref "U3") (pin "J14") (pinfunction "VSS_J14") (pintype "passive"))
      (node (ref "U3") (pin "J15") (pinfunction "VSS_J15") (pintype "passive"))
      (node (ref "U3") (pin "J4") (pinfunction "VSS_J4") (pintype "passive"))
      (node (ref "U3") (pin "J5") (pinfunction "VSS_J5") (pintype "passive"))
      (node (ref "U3") (pin "J7") (pinfunction "VSS_J7") (pintype "passive"))
      (node (ref "U3") (pin "J9") (pinfunction "VSS_J9") (pintype "passive"))
      (node (ref "U3") (pin "K12") (pinfunction "VSS_K12") (pintype "passive"))
      (node (ref "U3") (pin "K13") (pinfunction "VSS_K13") (pintype "passive"))
      (node (ref "U3") (pin "K14") (pinfunction "VSS_K14") (pintype "passive"))
      (node (ref "U3") (pin "K15") (pinfunction "VSS_K15") (pintype "passive"))
      (node (ref "U3") (pin "K16") (pinfunction "VSS_K16") (pintype "passive"))
      (node (ref "U3") (pin "K5") (pinfunction "VSS_K5") (pintype "passive"))
      (node (ref "U3") (pin "K7") (pinfunction "VSS_K7") (pintype "passive"))
      (node (ref "U3") (pin "K9") (pinfunction "VSS_K9") (pintype "passive"))
      (node (ref "U3") (pin "L12") (pinfunction "VSS_L12") (pintype "passive"))
      (node (ref "U3") (pin "L15") (pinfunction "VSS_L15") (pintype "passive"))
      (node (ref "U3") (pin "L3") (pinfunction "VSS_L3") (pintype "passive"))
      (node (ref "U3") (pin "L5") (pinfunction "VSS_L5") (pintype "passive"))
      (node (ref "U3") (pin "L7") (pinfunction "VSS_L7") (pintype "passive"))
      (node (ref "U3") (pin "L9") (pinfunction "VSS_L9") (pintype "passive"))
      (node (ref "U3") (pin "M11") (pinfunction "VSS_M11") (pintype "passive"))
      (node (ref "U3") (pin "M12") (pinfunction "VSS_M12") (pintype "passive"))
      (node (ref "U3") (pin "M3") (pinfunction "VSS_M3") (pintype "passive"))
      (node (ref "U3") (pin "M5") (pinfunction "VSS_M5") (pintype "passive"))
      (node (ref "U3") (pin "M7") (pinfunction "VSS_M7") (pintype "passive"))
      (node (ref "U3") (pin "M9") (pinfunction "VSS_M9") (pintype "passive"))
      (node (ref "U3") (pin "N12") (pinfunction "VSS_N12") (pintype "passive"))
      (node (ref "U3") (pin "N4") (pinfunction "VSS_N4") (pintype "passive"))
      (node (ref "U3") (pin "N6") (pinfunction "VSS_N6") (pintype "passive"))
      (node (ref "U3") (pin "N7") (pinfunction "VSS_N7") (pintype "passive"))
      (node (ref "U3") (pin "N9") (pinfunction "VSS_N9") (pintype "passive"))
      (node (ref "U3") (pin "P14") (pinfunction "VSS_P14") (pintype "passive"))
      (node (ref "U3") (pin "P7") (pinfunction "VSS_P7") (pintype "passive"))
      (node (ref "U3") (pin "P8") (pinfunction "VSS_P8") (pintype "passive"))
      (node (ref "U3") (pin "P9") (pinfunction "VSS_P9") (pintype "passive"))
      (node (ref "U3") (pin "R1") (pinfunction "VSS_R1") (pintype "passive"))
      (node (ref "U3") (pin "T13") (pinfunction "VSS_T13") (pintype "passive"))
      (node (ref "Y2") (pin "2") (pinfunction "NC_2") (pintype "passive"))
      (node (ref "Y2") (pin "4") (pinfunction "NC_4") (pintype "passive"))
    )
    (net (code "56") (name "Net-(Q1-D)") (class "Default")
      (node (ref "Q1") (pin "3") (pinfunction "D_3") (pintype "passive"))
      (node (ref "R59") (pin "2") (pinfunction "2_2") (pintype "passive"))
    )
    (net (code "57") (name "Net-(Q1-G)") (class "Default")
      (node (ref "Q1") (pin "1") (pinfunction "G_1") (pintype "passive"))
      (node (ref "Q2") (pin "3") (pinfunction "D_3") (pintype "passive"))
      (node (ref "R58") (pin "1") (pinfunction "1_1") (pintype "passive"))
    )
    (net (code "58") (name "Net-(Q2-G)") (class "Default")
      (node (ref "Q2") (pin "1") (pinfunction "G_1") (pintype "passive"))
      (node (ref "R60") (pin "1") (pinfunction "1_1") (pintype "passive"))
    )
    (net (code "59") (name "Net-(U3-ADC_1)") (class "Default")
      (node (ref "C92") (pin "1") (pinfunction "1_1") (pintype "passive"))
      (node (ref "R59") (pin "1") (pinfunction "1_1") (pintype "passive"))
      (node (ref "R61") (pin "2") (pinfunction "2_2") (pintype "passive"))
      (node (ref "U3") (pin "A6") (pinfunction "ADC_1_A6") (pintype "passive"))
    )
    (net (code "60") (name "Net-(U3-CODEC_VCM)") (class "Default")
      (node (ref "C100") (pin "1") (pinfunction "1_1") (pintype "passive"))
      (node (ref "C99") (pin "1") (pinfunction "1_1") (pintype "passive"))
      (node (ref "U3") (pin "B4") (pinfunction "CODEC_VCM_B4") (pintype "passive"))
    )
    (net (code "61") (name "Net-(U3-DDR_VREF)") (class "Default")
      (node (ref "C37") (pin "1") (pinfunction "1_1") (pintype "passive"))
      (node (ref "R33") (pin "2") (pinfunction "2_2") (pintype "passive"))
      (node (ref "R46") (pin "1") (pinfunction "1_1") (pintype "passive"))
      (node (ref "U3") (pin "H11") (pinfunction "DDR_VREF_H11") (pintype "passive"))
    )
    (net (code "62") (name "Net-(U3-DDR_ZN)") (class "Default")
      (node (ref "R48") (pin "1") (pinfunction "1_1") (pintype "passive"))
      (node (ref "U3") (pin "H16") (pinfunction "DDR_ZN_H16") (pintype "passive"))
    )
    (net (code "63") (name "Net-(U3-DDR_ZQ)") (class "Default")
      (node (ref "R47") (pin "1") (pinfunction "1_1") (pintype "passive"))
      (node (ref "U3") (pin "J16") (pinfunction "DDR_ZQ_J16") (pintype "passive"))
    )
    (net (code "64") (name "Net-(U3-GPIO15)") (class "Default")
      (node (ref "R42") (pin "1") (pinfunction "1_1") (pintype "passive"))
      (node (ref "U3") (pin "E1") (pinfunction "GPIO15_E1") (pintype "passive"))
    )
    (net (code "65") (name "Net-(U3-INT0)") (class "Default")
      (node (ref "R6") (pin "1") (pinfunction "1_1") (pintype "passive"))
      (node (ref "U3") (pin "C16") (pinfunction "INT0_C16") (pintype "passive"))
    )
    (net (code "66") (name "Net-(U3-INT1)") (class "Default")
      (node (ref "R20") (pin "2") (pinfunction "2_2") (pintype "passive"))
      (node (ref "U3") (pin "D14") (pinfunction "INT1_D14") (pintype "passive"))
    )
    (net (code "67") (name "Net-(U3-INT2)") (class "Default")
      (node (ref "R53") (pin "1") (pinfunction "1_1") (pintype "passive"))
      (node (ref "U3") (pin "E14") (pinfunction "INT2_E14") (pintype "passive"))
    )
    (net (code "68") (name "Net-(U3-INT4)") (class "Default")
      (node (ref "R45") (pin "1") (pinfunction "1_1") (pintype "passive"))
      (node (ref "U3") (pin "F14") (pinfunction "INT4_F14") (pintype "passive"))
    )
    (net (code "69") (name "Net-(U3-MICNL)") (class "Default")
      (node (ref "C101") (pin "2") (pinfunction "2_2") (pintype "passive"))
      (node (ref "U3") (pin "A5") (pinfunction "MICNL_A5") (pintype "passive"))
    )
    (net (code "70") (name "Net-(U3-MICPL)") (class "Default")
      (node (ref "C97") (pin "2") (pinfunction "2_2") (pintype "passive"))
      (node (ref "U3") (pin "B5") (pinfunction "MICPL_B5") (pintype "passive"))
    )
    (net (code "71") (name "Net-(U3-MIC_BIAS)") (class "Default")
      (node (ref "CB1") (pin "1") (pinfunction "1_1") (pintype "passive"))
      (node (ref "CB2") (pin "1") (pinfunction "1_1") (pintype "passive"))
      (node (ref "FB4") (pin "2") (pinfunction "2_2") (pintype "passive"))
      (node (ref "U3") (pin "A4") (pinfunction "MIC_BIAS_A4") (pintype "passive"))
    )
    (net (code "72") (name "Net-(U3-MIPI_REXT)") (class "Default")
      (node (ref "R37") (pin "2") (pinfunction "2_2") (pintype "passive"))
      (node (ref "U3") (pin "P6") (pinfunction "MIPI_REXT_P6") (pintype "passive"))
    )
    (net (code "73") (name "Net-(U3-USB0_TXRTUNE)") (class "Default")
      (node (ref "R62") (pin "1") (pinfunction "1_1") (pintype "passive"))
      (node (ref "U3") (pin "B9") (pinfunction "USB0_TXRTUNE_B9") (pintype "passive"))
    )
    (net (code "74") (name "Net-(U3-USB0_VBUS)") (class "Default")
      (node (ref "R63") (pin "1") (pinfunction "1_1") (pintype "passive"))
      (node (ref "U3") (pin "B7") (pinfunction "USB0_VBUS_B7") (pintype "passive"))
    )
    (net (code "75") (name "Net-(U13-OUT)") (class "Default")
      (node (ref "C97") (pin "1") (pinfunction "1_1") (pintype "passive"))
      (node (ref "C98") (pin "1") (pinfunction "1_1") (pintype "passive"))
      (node (ref "U13") (pin "2") (pinfunction "OUT_2") (pintype "passive"))
    )
    (net (code "76") (name "Net-(U13-VDD)") (class "Default")
      (node (ref "C95") (pin "2") (pinfunction "2_2") (pintype "passive"))
      (node (ref "C96") (pin "1") (pinfunction "1_1") (pintype "passive"))
      (node (ref "FB4") (pin "1") (pinfunction "1_1") (pintype "passive"))
      (node (ref "U13") (pin "1") (pinfunction "VDD_1") (pintype "passive"))
    )
    (net (code "77") (name "VBAT") (class "Default")
      (node (ref "Q1") (pin "2") (pinfunction "S_2") (pintype "passive"))
      (node (ref "R58") (pin "2") (pinfunction "2_2") (pintype "passive"))
    )
    (net (code "78") (name "VUSB") (class "Default")
      (node (ref "R63") (pin "2") (pinfunction "2_2") (pintype "passive"))
    )
    (net (code "79") (name "unconnected-(U3-ADC_0-PadA7)") (class "Default")
      (node (ref "U3") (pin "A7") (pinfunction "ADC_0_A7") (pintype "passive+no_connect"))
    )
    (net (code "80") (name "unconnected-(U3-ADC_2-PadB6)") (class "Default")
      (node (ref "U3") (pin "B6") (pinfunction "ADC_2_B6") (pintype "passive+no_connect"))
    )
    (net (code "81") (name "unconnected-(U3-GPIO3-PadN15)") (class "Default")
      (node (ref "U3") (pin "N15") (pinfunction "GPIO3_N15") (pintype "passive+no_connect"))
    )
    (net (code "82") (name "unconnected-(U3-GPIO4-PadN14)") (class "Default")
      (node (ref "U3") (pin "N14") (pinfunction "GPIO4_N14") (pintype "passive+no_connect"))
    )
    (net (code "83") (name "unconnected-(U3-GPIO5-PadM14)") (class "Default")
      (node (ref "U3") (pin "M14") (pinfunction "GPIO5_M14") (pintype "passive+no_connect"))
    )
    (net (code "84") (name "unconnected-(U3-GPIO6-PadN13)") (class "Default")
      (node (ref "U3") (pin "N13") (pinfunction "GPIO6_N13") (pintype "passive+no_connect"))
    )
    (net (code "85") (name "unconnected-(U3-GPIO10-PadP15)") (class "Default")
      (node (ref "U3") (pin "P15") (pinfunction "GPIO10_P15") (pintype "passive+no_connect"))
    )
    (net (code "86") (name "unconnected-(U3-GPIO11-PadP16)") (class "Default")
      (node (ref "U3") (pin "P16") (pinfunction "GPIO11_P16") (pintype "passive+no_connect"))
    )
    (net (code "87") (name "unconnected-(U3-GPIO12-PadP13)") (class "Default")
      (node (ref "U3") (pin "P13") (pinfunction "GPIO12_P13") (pintype "passive+no_connect"))
    )
    (net (code "88") (name "unconnected-(U3-GPIO13-PadP12)") (class "Default")
      (node (ref "U3") (pin "P12") (pinfunction "GPIO13_P12") (pintype "passive+no_connect"))
    )
    (net (code "89") (name "unconnected-(U3-GPIO20-PadH2)") (class "Default")
      (node (ref "U3") (pin "H2") (pinfunction "GPIO20_H2") (pintype "passive+no_connect"))
    )
    (net (code "90") (name "unconnected-(U3-GPIO21-PadH1)") (class "Default")
      (node (ref "U3") (pin "H1") (pinfunction "GPIO21_H1") (pintype "passive+no_connect"))
    )
    (net (code "91") (name "unconnected-(U3-GPIO22-PadJ1)") (class "Default")
      (node (ref "U3") (pin "J1") (pinfunction "GPIO22_J1") (pintype "passive+no_connect"))
    )
    (net (code "92") (name "unconnected-(U3-GPIO23-PadJ2)") (class "Default")
      (node (ref "U3") (pin "J2") (pinfunction "GPIO23_J2") (pintype "passive+no_connect"))
    )
    (net (code "93") (name "unconnected-(U3-GPIO24-PadJ3)") (class "Default")
      (node (ref "U3") (pin "J3") (pinfunction "GPIO24_J3") (pintype "passive+no_connect"))
    )
    (net (code "94") (name "unconnected-(U3-GPIO25-PadK3)") (class "Default")
      (node (ref "U3") (pin "K3") (pinfunction "GPIO25_K3") (pintype "passive+no_connect"))
    )
    (net (code "95") (name "unconnected-(U3-GPIO26-PadP11)") (class "Default")
      (node (ref "U3") (pin "P11") (pinfunction "GPIO26_P11") (pintype "passive+no_connect"))
    )
    (net (code "96") (name "unconnected-(U3-GPIO27-PadP10)") (class "Default")
      (node (ref "U3") (pin "P10") (pinfunction "GPIO27_P10") (pintype "passive+no_connect"))
    )
    (net (code "97") (name "unconnected-(U3-GPIO28-PadR16)") (class "Default")
      (node (ref "U3") (pin "R16") (pinfunction "GPIO28_R16") (pintype "passive+no_connect"))
    )
    (net (code "98") (name "unconnected-(U3-GPIO29-PadR15)") (class "Default")
      (node (ref "U3") (pin "R15") (pinfunction "GPIO29_R15") (pintype "passive+no_connect"))
    )
    (net (code "99") (name "unconnected-(U3-GPIO30-PadR14)") (class "Default")
      (node (ref "U3") (pin "R14") (pinfunction "GPIO30_R14") (pintype "passive+no_connect"))
    )
    (net (code "100") (name "unconnected-(U3-GPIO31-PadR13)") (class "Default")
      (node (ref "U3") (pin "R13") (pinfunction "GPIO31_R13") (pintype "passive+no_connect"))
    )
    (net (code "101") (name "unconnected-(U3-GPIO32-PadR12)") (class "Default")
      (node (ref "U3") (pin "R12") (pinfunction "GPIO32_R12") (pintype "passive+no_connect"))
    )
    (net (code "102") (name "unconnected-(U3-GPIO33-PadR11)") (class "Default")
      (node (ref "U3") (pin "R11") (pinfunction "GPIO33_R11") (pintype "passive+no_connect"))
    )
    (net (code "103") (name "unconnected-(U3-GPIO34-PadT15)") (class "Default")
      (node (ref "U3") (pin "T15") (pinfunction "GPIO34_T15") (pintype "passive+no_connect"))
    )
    (net (code "104") (name "unconnected-(U3-GPIO35-PadT14)") (class "Default")
      (node (ref "U3") (pin "T14") (pinfunction "GPIO35_T14") (pintype "passive+no_connect"))
    )
    (net (code "105") (name "unconnected-(U3-GPIO36-PadT12)") (class "Default")
      (node (ref "U3") (pin "T12") (pinfunction "GPIO36_T12") (pintype "passive+no_connect"))
    )
    (net (code "106") (name "unconnected-(U3-GPIO37-PadT11)") (class "Default")
      (node (ref "U3") (pin "T11") (pinfunction "GPIO37_T11") (pintype "passive+no_connect"))
    )
    (net (code "107") (name "unconnected-(U3-GPIO44-PadB1)") (class "Default")
      (node (ref "U3") (pin "B1") (pinfunction "GPIO44_B1") (pintype "passive+no_connect"))
    )
    (net (code "108") (name "unconnected-(U3-GPIO45-PadC2)") (class "Default")
      (node (ref "U3") (pin "C2") (pinfunction "GPIO45_C2") (pintype "passive+no_connect"))
    )
    (net (code "109") (name "unconnected-(U3-GPIO59-PadP4)") (class "Default")
      (node (ref "U3") (pin "P4") (pinfunction "GPIO59_P4") (pintype "passive+no_connect"))
    )
    (net (code "110") (name "unconnected-(U3-HPOUTL-PadA2)") (class "Default")
      (node (ref "U3") (pin "A2") (pinfunction "HPOUTL_A2") (pintype "passive+no_connect"))
    )
    (net (code "111") (name "unconnected-(U3-HPOUTR-PadB2)") (class "Default")
      (node (ref "U3") (pin "B2") (pinfunction "HPOUTR_B2") (pintype "passive+no_connect"))
    )
    (net (code "112") (name "unconnected-(U3-MIPI_ATB-PadP5)") (class "Default")
      (node (ref "U3") (pin "P5") (pinfunction "MIPI_ATB_P5") (pintype "passive+no_connect"))
    )
    (net (code "113") (name "unconnected-(U3-MIPI_RX1_CLK_N-PadR4)") (class "Default")
      (node (ref "U3") (pin "R4") (pinfunction "MIPI_RX1_CLK_N_R4") (pintype "passive+no_connect"))
    )
    (net (code "114") (name "unconnected-(U3-MIPI_RX1_CLK_P-PadT4)") (class "Default")
      (node (ref "U3") (pin "T4") (pinfunction "MIPI_RX1_CLK_P_T4") (pintype "passive+no_connect"))
    )
    (net (code "115") (name "unconnected-(U3-MIPI_RX1_D2_N-PadT3)") (class "Default")
      (node (ref "U3") (pin "T3") (pinfunction "MIPI_RX1_D2_N_T3") (pintype "passive+no_connect"))
    )
    (net (code "116") (name "unconnected-(U3-MIPI_RX1_D2_P-PadR3)") (class "Default")
      (node (ref "U3") (pin "R3") (pinfunction "MIPI_RX1_D2_P_R3") (pintype "passive+no_connect"))
    )
    (net (code "117") (name "unconnected-(U3-MIPI_RX1_D3_N-PadR5)") (class "Default")
      (node (ref "U3") (pin "R5") (pinfunction "MIPI_RX1_D3_N_R5") (pintype "passive+no_connect"))
    )
    (net (code "118") (name "unconnected-(U3-MIPI_RX1_D3_P-PadT5)") (class "Default")
      (node (ref "U3") (pin "T5") (pinfunction "MIPI_RX1_D3_P_T5") (pintype "passive+no_connect"))
    )
    (net (code "119") (name "unconnected-(U3-MIPI_TX0_CLK_N-PadR9)") (class "Default")
      (node (ref "U3") (pin "R9") (pinfunction "MIPI_TX0_CLK_N_R9") (pintype "passive+no_connect"))
    )
    (net (code "120") (name "unconnected-(U3-MIPI_TX0_CLK_P-PadT9)") (class "Default")
      (node (ref "U3") (pin "T9") (pinfunction "MIPI_TX0_CLK_P_T9") (pintype "passive+no_connect"))
    )
    (net (code "121") (name "unconnected-(U3-MIPI_TX0_D0_N-PadR8)") (class "Default")
      (node (ref "U3") (pin "R8") (pinfunction "MIPI_TX0_D0_N_R8") (pintype "passive+no_connect"))
    )
    (net (code "122") (name "unconnected-(U3-MIPI_TX0_D0_P-PadT8)") (class "Default")
      (node (ref "U3") (pin "T8") (pinfunction "MIPI_TX0_D0_P_T8") (pintype "passive+no_connect"))
    )
    (net (code "123") (name "unconnected-(U3-MIPI_TX0_D1_N-PadR10)") (class "Default")
      (node (ref "U3") (pin "R10") (pinfunction "MIPI_TX0_D1_N_R10") (pintype "passive+no_connect"))
    )
    (net (code "124") (name "unconnected-(U3-MIPI_TX0_D1_P-PadT10)") (class "Default")
      (node (ref "U3") (pin "T10") (pinfunction "MIPI_TX0_D1_P_T10") (pintype "passive+no_connect"))
    )
    (net (code "125") (name "unconnected-(U3-MIPI_TX1_D2_N-PadT7)") (class "Default")
      (node (ref "U3") (pin "T7") (pinfunction "MIPI_TX1_D2_N_T7") (pintype "passive+no_connect"))
    )
    (net (code "126") (name "unconnected-(U3-MIPI_TX1_D2_P-PadR7)") (class "Default")
      (node (ref "U3") (pin "R7") (pinfunction "MIPI_TX1_D2_P_R7") (pintype "passive+no_connect"))
    )
    (net (code "127") (name "unconnected-(U3-MIPI_TX1_D3_N-PadR6)") (class "Default")
      (node (ref "U3") (pin "R6") (pinfunction "MIPI_TX1_D3_N_R6") (pintype "passive+no_connect"))
    )
    (net (code "128") (name "unconnected-(U3-MIPI_TX1_D3_P-PadT6)") (class "Default")
      (node (ref "U3") (pin "T6") (pinfunction "MIPI_TX1_D3_P_T6") (pintype "passive+no_connect"))
    )
    (net (code "129") (name "unconnected-(U3-MMC0_D4-PadB13)") (class "Default")
      (node (ref "U3") (pin "B13") (pinfunction "MMC0_D4_B13") (pintype "passive+no_connect"))
    )
    (net (code "130") (name "unconnected-(U3-MMC0_D5-PadB10)") (class "Default")
      (node (ref "U3") (pin "B10") (pinfunction "MMC0_D5_B10") (pintype "passive+no_connect"))
    )
    (net (code "131") (name "unconnected-(U3-MMC0_D6-PadB11)") (class "Default")
      (node (ref "U3") (pin "B11") (pinfunction "MMC0_D6_B11") (pintype "passive+no_connect"))
    )
    (net (code "132") (name "unconnected-(U3-MMC0_D7-PadB12)") (class "Default")
      (node (ref "U3") (pin "B12") (pinfunction "MMC0_D7_B12") (pintype "passive+no_connect"))
    )
    (net (code "133") (name "unconnected-(U3-MMC0_RST_N-PadC11)") (class "Default")
      (node (ref "U3") (pin "C11") (pinfunction "MMC0_RST_N_C11") (pintype "output+no_connect"))
    )
    (net (code "134") (name "unconnected-(U3-MMC0_STROBE-PadC10)") (class "Default")
      (node (ref "U3") (pin "C10") (pinfunction "MMC0_STROBE_C10") (pintype "passive+no_connect"))
    )
    (net (code "135") (name "unconnected-(U3-NC-PadA1)") (class "Default")
      (node (ref "U3") (pin "A1") (pinfunction "NC_A1") (pintype "passive+no_connect"))
    )
    (net (code "136") (name "unconnected-(U3-NC-PadA16)") (class "Default")
      (node (ref "U3") (pin "A16") (pinfunction "NC_A16") (pintype "passive+no_connect"))
    )
    (net (code "137") (name "unconnected-(U3-NC-PadT1)") (class "Default")
      (node (ref "U3") (pin "T1") (pinfunction "NC_T1") (pintype "passive+no_connect"))
    )
    (net (code "138") (name "unconnected-(U3-NC-PadT16)") (class "Default")
      (node (ref "U3") (pin "T16") (pinfunction "NC_T16") (pintype "passive+no_connect"))
    )
    (net (code "139") (name "unconnected-(U3-OUT0-PadF13)") (class "Default")
      (node (ref "U3") (pin "F13") (pinfunction "OUT0_F13") (pintype "output+no_connect"))
    )
    (net (code "140") (name "unconnected-(U3-OUT1-PadE13)") (class "Default")
      (node (ref "U3") (pin "E13") (pinfunction "OUT1_E13") (pintype "passive+no_connect"))
    )
    (net (code "141") (name "unconnected-(U3-USB0_ID-PadA9)") (class "Default")
      (node (ref "U3") (pin "A9") (pinfunction "USB0_ID_A9") (pintype "passive+no_connect"))
    )
  )
)
